# boombox_routed.net
KiCad netlist of a schematic drawn in EAGLE
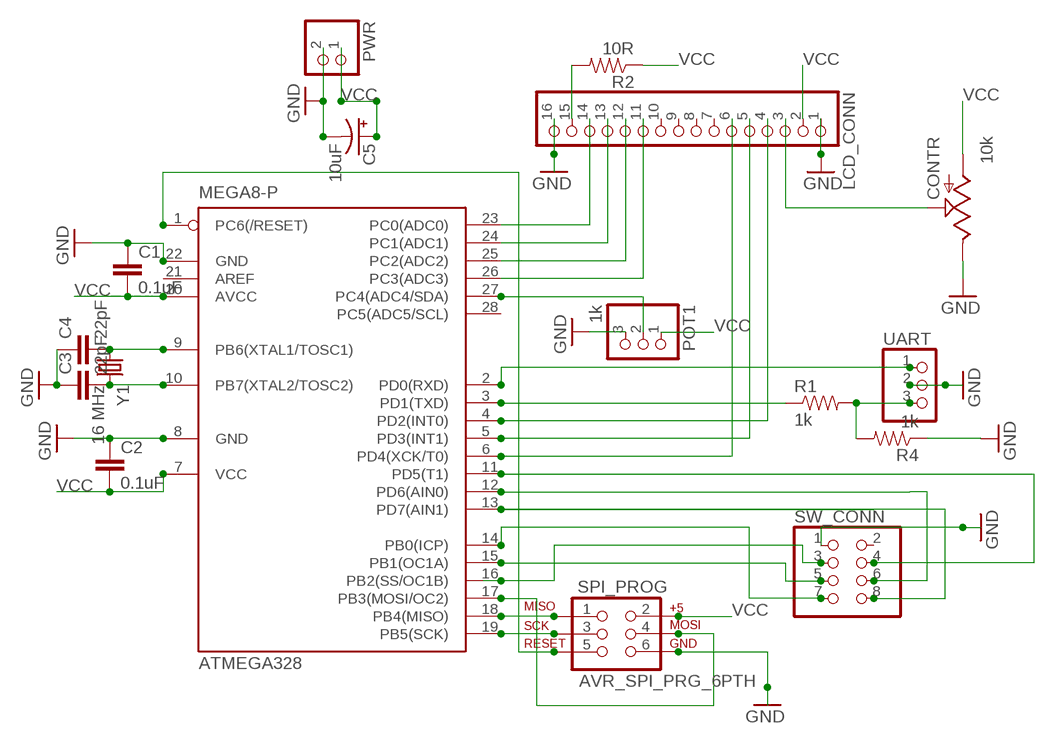
[diagram p0: schematic, sheet 1]

(export (version "E")
  (design (tool "Eeschema 10.0.6"))
  (components
    (comp (ref "ATMEGA328")
      (value "MEGA8-P")
      (footprint "eagle-import:DIL28-3")
      (libsource (lib "eagle-import") (part "MEGA8-P"))
    )
    (comp (ref "C1")
      (value "0.1uF")
      (footprint "eagle-import:C2.5-2")
      (libsource (lib "eagle-import") (part "C2.5/2"))
    )
    (comp (ref "C2")
      (value "0.1uF")
      (footprint "eagle-import:C2.5-2")
      (libsource (lib "eagle-import") (part "C2.5/2"))
    )
    (comp (ref "C3")
      (value "22pF")
      (footprint "eagle-import:C2.5-2")
      (libsource (lib "eagle-import") (part "C2.5/2"))
    )
    (comp (ref "C4")
      (value "22pF")
      (footprint "eagle-import:C2.5-2")
      (libsource (lib "eagle-import") (part "C2.5/2"))
    )
    (comp (ref "C5")
      (value "10uF")
      (footprint "eagle-import:CPOL-RADIAL-10UF-25V")
      (libsource (lib "eagle-import") (part "CAP_POLPTH2"))
    )
    (comp (ref "CONTR")
      (value "10k")
      (footprint "eagle-import:3362U")
      (libsource (lib "eagle-import") (part "POT100K_3362U"))
    )
    (comp (ref "LCD_CONN")
      (value "PINHD-1X16")
      (footprint "eagle-import:1X16")
      (libsource (lib "eagle-import") (part "PINHD-1X16"))
    )
    (comp (ref "POT1")
      (value "1k")
      (footprint "eagle-import:1X03")
      (libsource (lib "eagle-import") (part "PINHD-1X3"))
    )
    (comp (ref "PWR")
      (value "PINHD-1X2")
      (footprint "eagle-import:1X02")
      (libsource (lib "eagle-import") (part "PINHD-1X2"))
    )
    (comp (ref "R1")
      (value "1k")
      (footprint "eagle-import:AXIAL-0.4")
      (libsource (lib "eagle-import") (part "RESISTORPTH-1/4W"))
    )
    (comp (ref "R2")
      (value "10R")
      (footprint "eagle-import:AXIAL-0.4")
      (libsource (lib "eagle-import") (part "RESISTORPTH-1/4W"))
    )
    (comp (ref "R4")
      (value "1k")
      (footprint "eagle-import:AXIAL-0.4")
      (libsource (lib "eagle-import") (part "RESISTORPTH-1/4W"))
    )
    (comp (ref "SPI_PROG")
      (value "AVR_SPI_PRG_6PTH")
      (footprint "eagle-import:2X3")
      (libsource (lib "eagle-import") (part "AVR_SPI_PRG_6PTH"))
    )
    (comp (ref "SW_CONN")
      (value "PINHD-2X4")
      (footprint "eagle-import:2X04")
      (libsource (lib "eagle-import") (part "PINHD-2X4"))
    )
    (comp (ref "UART")
      (value "PINHD-1X3")
      (footprint "eagle-import:1X03")
      (libsource (lib "eagle-import") (part "PINHD-1X3"))
    )
    (comp (ref "Y1")
      (value "16 MHz")
      (footprint "eagle-import:HC49US")
      (libsource (lib "eagle-import") (part "CRYSTALHC49US"))
    )
  )
  (nets
    (net (code "1") (name "/VCC") (class "Default")
      (node (ref "ATMEGA328") (pin "20") (pinfunction "AVCC_20") (pintype "power_in"))
      (node (ref "ATMEGA328") (pin "7") (pinfunction "VCC_7") (pintype "power_in"))
      (node (ref "C1") (pin "2") (pinfunction "2_2") (pintype "passive"))
      (node (ref "C2") (pin "2") (pinfunction "2_2") (pintype "passive"))
      (node (ref "C5") (pin "1") (pinfunction "+_1") (pintype "passive"))
      (node (ref "CONTR") (pin "P$3") (pinfunction "A_P$3") (pintype "passive"))
      (node (ref "LCD_CONN") (pin "2") (pinfunction "2_2") (pintype "passive"))
      (node (ref "POT1") (pin "1") (pinfunction "1_1") (pintype "passive"))
      (node (ref "PWR") (pin "1") (pinfunction "1_1") (pintype "passive"))
      (node (ref "R2") (pin "P$1") (pinfunction "1_P$1") (pintype "passive"))
      (node (ref "SPI_PROG") (pin "2") (pinfunction "2_2") (pintype "passive"))
    )
    (net (code "2") (name "GND") (class "Default")
      (node (ref "ATMEGA328") (pin "22") (pinfunction "GND_22") (pintype "power_in"))
      (node (ref "ATMEGA328") (pin "8") (pinfunction "GND_8") (pintype "power_in"))
      (node (ref "C1") (pin "1") (pinfunction "1_1") (pintype "passive"))
      (node (ref "C2") (pin "1") (pinfunction "1_1") (pintype "passive"))
      (node (ref "C3") (pin "1") (pinfunction "1_1") (pintype "passive"))
      (node (ref "C4") (pin "1") (pinfunction "1_1") (pintype "passive"))
      (node (ref "C5") (pin "2") (pinfunction "-_2") (pintype "passive"))
      (node (ref "CONTR") (pin "P$1") (pinfunction "E_P$1") (pintype "passive"))
      (node (ref "LCD_CONN") (pin "1") (pinfunction "1_1") (pintype "passive"))
      (node (ref "LCD_CONN") (pin "16") (pinfunction "16_16") (pintype "passive"))
      (node (ref "POT1") (pin "3") (pinfunction "3_3") (pintype "passive"))
      (node (ref "PWR") (pin "2") (pinfunction "2_2") (pintype "passive"))
      (node (ref "R4") (pin "P$1") (pinfunction "1_P$1") (pintype "passive"))
      (node (ref "SPI_PROG") (pin "6") (pinfunction "6_6") (pintype "passive"))
      (node (ref "SW_CONN") (pin "1") (pinfunction "1_1") (pintype "passive"))
      (node (ref "UART") (pin "2") (pinfunction "2_2") (pintype "passive"))
    )
    (net (code "3") (name "Net-(ATMEGA328-PB0(ICP))") (class "Default")
      (node (ref "ATMEGA328") (pin "14") (pinfunction "PB0(ICP)_14") (pintype "bidirectional"))
      (node (ref "SW_CONN") (pin "7") (pinfunction "7_7") (pintype "passive"))
    )
    (net (code "4") (name "Net-(ATMEGA328-PB1(OC1A))") (class "Default")
      (node (ref "ATMEGA328") (pin "15") (pinfunction "PB1(OC1A)_15") (pintype "bidirectional"))
      (node (ref "SW_CONN") (pin "5") (pinfunction "5_5") (pintype "passive"))
    )
    (net (code "5") (name "Net-(ATMEGA328-PB2(SS{slash}OC1B))") (class "Default")
      (node (ref "ATMEGA328") (pin "16") (pinfunction "PB2(SS/OC1B)_16") (pintype "bidirectional"))
      (node (ref "SW_CONN") (pin "3") (pinfunction "3_3") (pintype "passive"))
    )
    (net (code "6") (name "Net-(ATMEGA328-PB3(MOSI{slash}OC2))") (class "Default")
      (node (ref "ATMEGA328") (pin "17") (pinfunction "PB3(MOSI/OC2)_17") (pintype "bidirectional"))
      (node (ref "SPI_PROG") (pin "4") (pinfunction "4_4") (pintype "passive"))
    )
    (net (code "7") (name "Net-(ATMEGA328-PB4(MISO))") (class "Default")
      (node (ref "ATMEGA328") (pin "18") (pinfunction "PB4(MISO)_18") (pintype "bidirectional"))
      (node (ref "SPI_PROG") (pin "1") (pinfunction "1_1") (pintype "passive"))
    )
    (net (code "8") (name "Net-(ATMEGA328-PB5(SCK))") (class "Default")
      (node (ref "ATMEGA328") (pin "19") (pinfunction "PB5(SCK)_19") (pintype "bidirectional"))
      (node (ref "SPI_PROG") (pin "3") (pinfunction "3_3") (pintype "passive"))
    )
    (net (code "9") (name "Net-(ATMEGA328-PB6(XTAL1{slash}TOSC1))") (class "Default")
      (node (ref "ATMEGA328") (pin "9") (pinfunction "PB6(XTAL1/TOSC1)_9") (pintype "bidirectional"))
      (node (ref "C4") (pin "2") (pinfunction "2_2") (pintype "passive"))
      (node (ref "Y1") (pin "1") (pinfunction "1_1") (pintype "passive"))
    )
    (net (code "10") (name "Net-(ATMEGA328-PB7(XTAL2{slash}TOSC2))") (class "Default")
      (node (ref "ATMEGA328") (pin "10") (pinfunction "PB7(XTAL2/TOSC2)_10") (pintype "bidirectional"))
      (node (ref "C3") (pin "2") (pinfunction "2_2") (pintype "passive"))
      (node (ref "Y1") (pin "2") (pinfunction "2_2") (pintype "passive"))
    )
    (net (code "11") (name "Net-(ATMEGA328-PC0(ADC0))") (class "Default")
      (node (ref "ATMEGA328") (pin "23") (pinfunction "PC0(ADC0)_23") (pintype "bidirectional"))
      (node (ref "LCD_CONN") (pin "14") (pinfunction "14_14") (pintype "passive"))
    )
    (net (code "12") (name "Net-(ATMEGA328-PC1(ADC1))") (class "Default")
      (node (ref "ATMEGA328") (pin "24") (pinfunction "PC1(ADC1)_24") (pintype "bidirectional"))
      (node (ref "LCD_CONN") (pin "13") (pinfunction "13_13") (pintype "passive"))
    )
    (net (code "13") (name "Net-(ATMEGA328-PC2(ADC2))") (class "Default")
      (node (ref "ATMEGA328") (pin "25") (pinfunction "PC2(ADC2)_25") (pintype "bidirectional"))
      (node (ref "LCD_CONN") (pin "12") (pinfunction "12_12") (pintype "passive"))
    )
    (net (code "14") (name "Net-(ATMEGA328-PC3(ADC3))") (class "Default")
      (node (ref "ATMEGA328") (pin "26") (pinfunction "PC3(ADC3)_26") (pintype "bidirectional"))
      (node (ref "LCD_CONN") (pin "11") (pinfunction "11_11") (pintype "passive"))
    )
    (net (code "15") (name "Net-(ATMEGA328-PC4(ADC4{slash}SDA))") (class "Default")
      (node (ref "ATMEGA328") (pin "27") (pinfunction "PC4(ADC4/SDA)_27") (pintype "bidirectional"))
      (node (ref "POT1") (pin "2") (pinfunction "2_2") (pintype "passive"))
    )
    (net (code "16") (name "Net-(ATMEGA328-PC6({slash}RESET))") (class "Default")
      (node (ref "ATMEGA328") (pin "1") (pinfunction "PC6(/RESET)_1") (pintype "bidirectional"))
      (node (ref "SPI_PROG") (pin "5") (pinfunction "5_5") (pintype "passive"))
    )
    (net (code "17") (name "Net-(ATMEGA328-PD0(RXD))") (class "Default")
      (node (ref "ATMEGA328") (pin "2") (pinfunction "PD0(RXD)_2") (pintype "bidirectional"))
      (node (ref "UART") (pin "1") (pinfunction "1_1") (pintype "passive"))
    )
    (net (code "18") (name "Net-(ATMEGA328-PD1(TXD))") (class "Default")
      (node (ref "ATMEGA328") (pin "3") (pinfunction "PD1(TXD)_3") (pintype "bidirectional"))
      (node (ref "R1") (pin "P$1") (pinfunction "1_P$1") (pintype "passive"))
    )
    (net (code "19") (name "Net-(ATMEGA328-PD2(INT0))") (class "Default")
      (node (ref "ATMEGA328") (pin "4") (pinfunction "PD2(INT0)_4") (pintype "bidirectional"))
      (node (ref "LCD_CONN") (pin "4") (pinfunction "4_4") (pintype "passive"))
    )
    (net (code "20") (name "Net-(ATMEGA328-PD3(INT1))") (class "Default")
      (node (ref "ATMEGA328") (pin "5") (pinfunction "PD3(INT1)_5") (pintype "bidirectional"))
      (node (ref "LCD_CONN") (pin "5") (pinfunction "5_5") (pintype "passive"))
    )
    (net (code "21") (name "Net-(ATMEGA328-PD4(XCK{slash}T0))") (class "Default")
      (node (ref "ATMEGA328") (pin "6") (pinfunction "PD4(XCK/T0)_6") (pintype "bidirectional"))
      (node (ref "LCD_CONN") (pin "6") (pinfunction "6_6") (pintype "passive"))
    )
    (net (code "22") (name "Net-(ATMEGA328-PD5(T1))") (class "Default")
      (node (ref "ATMEGA328") (pin "11") (pinfunction "PD5(T1)_11") (pintype "bidirectional"))
      (node (ref "SW_CONN") (pin "4") (pinfunction "4_4") (pintype "passive"))
    )
    (net (code "23") (name "Net-(ATMEGA328-PD6(AIN0))") (class "Default")
      (node (ref "ATMEGA328") (pin "12") (pinfunction "PD6(AIN0)_12") (pintype "bidirectional"))
      (node (ref "SW_CONN") (pin "6") (pinfunction "6_6") (pintype "passive"))
    )
    (net (code "24") (name "Net-(ATMEGA328-PD7(AIN1))") (class "Default")
      (node (ref "ATMEGA328") (pin "13") (pinfunction "PD7(AIN1)_13") (pintype "bidirectional"))
      (node (ref "SW_CONN") (pin "8") (pinfunction "8_8") (pintype "passive"))
    )
    (net (code "25") (name "Net-(CONTR-S)") (class "Default")
      (node (ref "CONTR") (pin "P$2") (pinfunction "S_P$2") (pintype "passive"))
      (node (ref "LCD_CONN") (pin "3") (pinfunction "3_3") (pintype "passive"))
    )
    (net (code "26") (name "Net-(R1-2)") (class "Default")
      (node (ref "R1") (pin "P$2") (pinfunction "2_P$2") (pintype "passive"))
      (node (ref "R4") (pin "P$2") (pinfunction "2_P$2") (pintype "passive"))
      (node (ref "UART") (pin "3") (pinfunction "3_3") (pintype "passive"))
    )
    (net (code "27") (name "Net-(R2-2)") (class "Default")
      (node (ref "LCD_CONN") (pin "15") (pinfunction "15_15") (pintype "passive"))
      (node (ref "R2") (pin "P$2") (pinfunction "2_P$2") (pintype "passive"))
    )
    (net (code "28") (name "unconnected-(ATMEGA328-AREF-Pad21)") (class "Default")
      (node (ref "ATMEGA328") (pin "21") (pinfunction "AREF_21") (pintype "passive"))
    )
    (net (code "29") (name "unconnected-(ATMEGA328-PC5(ADC5{slash}SCL)-Pad28)") (class "Default")
      (node (ref "ATMEGA328") (pin "28") (pinfunction "PC5(ADC5/SCL)_28") (pintype "bidirectional"))
    )
    (net (code "30") (name "unconnected-(LCD_CONN-Pad7)") (class "Default")
      (node (ref "LCD_CONN") (pin "7") (pinfunction "7_7") (pintype "passive"))
    )
    (net (code "31") (name "unconnected-(LCD_CONN-Pad8)") (class "Default")
      (node (ref "LCD_CONN") (pin "8") (pinfunction "8_8") (pintype "passive"))
    )
    (net (code "32") (name "unconnected-(LCD_CONN-Pad9)") (class "Default")
      (node (ref "LCD_CONN") (pin "9") (pinfunction "9_9") (pintype "passive"))
    )
    (net (code "33") (name "unconnected-(LCD_CONN-Pad10)") (class "Default")
      (node (ref "LCD_CONN") (pin "10") (pinfunction "10_10") (pintype "passive"))
    )
    (net (code "34") (name "unconnected-(SW_CONN-Pad2)") (class "Default")
      (node (ref "SW_CONN") (pin "2") (pinfunction "2_2") (pintype "passive"))
    )
  )
)
